# Power.net
KiCad netlist of a schematic drawn in Altium Designer
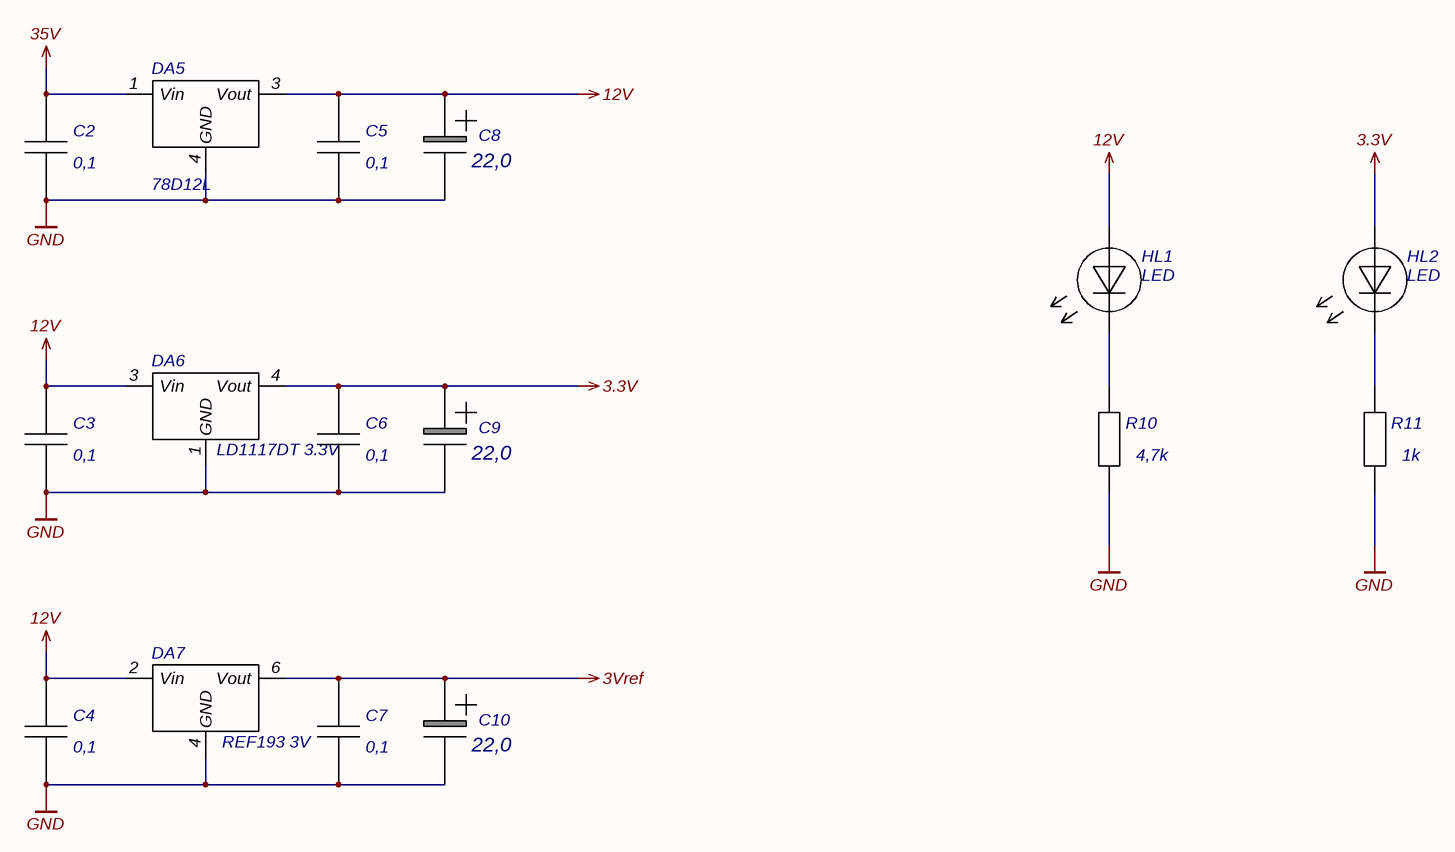
[diagram p0: Power.SchDoc]

(export (version "E")
  (design (tool "Eeschema 10.0.6"))
  (components
    (comp (ref "C2")
      (value "0,1")
      (footprint "С0805")
      (description "Чип-конденсатор")
      (libsource (lib "Passive") (part "Chip Capasitor"))
    )
    (comp (ref "C3")
      (value "0,1")
      (footprint "С0805")
      (description "Чип-конденсатор")
      (libsource (lib "Passive") (part "Chip Capasitor"))
    )
    (comp (ref "C4")
      (value "0,1")
      (footprint "С0805")
      (description "Чип-конденсатор")
      (libsource (lib "Passive") (part "Chip Capasitor"))
    )
    (comp (ref "C5")
      (value "0,1")
      (footprint "С0805")
      (description "Чип-конденсатор")
      (libsource (lib "Passive") (part "Chip Capasitor"))
    )
    (comp (ref "C6")
      (value "0,1")
      (footprint "С0805")
      (description "Чип-конденсатор")
      (libsource (lib "Passive") (part "Chip Capasitor"))
    )
    (comp (ref "C7")
      (value "0,1")
      (footprint "С0805")
      (description "Чип-конденсатор")
      (libsource (lib "Passive") (part "Chip Capasitor"))
    )
    (comp (ref "C8")
      (value "22,0")
      (footprint "C_tant 3(С-type)")
      (description "Чип конденсатор (3/C) тант.")
      (fields (field (name "MANUFACTURER") "KEMET") (field (name "PARTNUMBER") "Т491С226К010АТ"))
      (libsource (lib "Passive") (part "К53-67 (3/C)"))
    )
    (comp (ref "C9")
      (value "22,0")
      (footprint "C_tant 3(С-type)")
      (description "Чип конденсатор (3/C) тант.")
      (fields (field (name "MANUFACTURER") "KEMET") (field (name "PARTNUMBER") "Т491С226К010АТ"))
      (libsource (lib "Passive") (part "К53-67 (3/C)"))
    )
    (comp (ref "C10")
      (value "22,0")
      (footprint "C_tant 3(С-type)")
      (description "Чип конденсатор (3/C) тант.")
      (fields (field (name "MANUFACTURER") "KEMET") (field (name "PARTNUMBER") "Т491С226К010АТ"))
      (libsource (lib "Passive") (part "К53-67 (3/C)"))
    )
    (comp (ref "DA5")
      (value "78D12L")
      (footprint "DPAK")
      (description "Стабилизатор напряжения, 12В")
      (fields (field (name "MANUFACTURER") "UTD Semiconductor Co.,Ltd"))
      (libsource (lib "Schlib") (part "78D12L"))
    )
    (comp (ref "DA6")
      (value "LD1117DT 3.3V")
      (footprint "DPAK")
      (description "LDO-регулятор напряжения, 3.3В")
      (fields (field (name "MANUFACTURER") "STMicroelectronics"))
      (libsource (lib "Schlib") (part "LD1117DT33TR"))
    )
    (comp (ref "DA7")
      (value "REF193 3V")
      (footprint "SOP-8 (SOIC)")
      (description "Источник опорного напряжения, 3В")
      (fields (field (name "MANUFACTURER") "Analog Devices"))
      (libsource (lib "Schlib") (part "REF193"))
    )
    (comp (ref "HL1")
      (value "LED")
      (footprint "LED 5mm (L-7113IT)")
      (description "Светодиод, d=5мм")
      (fields (field (name "MANUFACTURER") "Kingbright"))
      (libsource (lib "Schlib") (part "LED"))
    )
    (comp (ref "HL2")
      (value "LED")
      (footprint "LED 5mm (L-7113IT)")
      (description "Светодиод, d=5мм")
      (fields (field (name "MANUFACTURER") "Kingbright"))
      (libsource (lib "Schlib") (part "LED"))
    )
    (comp (ref "R10")
      (value "4,7k")
      (footprint "R0603")
      (description "Чип-резистор")
      (libsource (lib "Passive") (part "Chip Resistor"))
    )
    (comp (ref "R11")
      (value "1k")
      (footprint "R0603")
      (description "Чип-резистор")
      (libsource (lib "Passive") (part "Chip Resistor"))
    )
  )
  (nets
    (net (code "1") (name "3.3V") (class "Default")
      (node (ref "C6") (pin "2") (pinfunction "2_2") (pintype "passive"))
      (node (ref "C9") (pin "1") (pinfunction "1_1") (pintype "passive"))
      (node (ref "DA6") (pin "4") (pinfunction "Vout_4") (pintype "passive"))
      (node (ref "HL2") (pin "2") (pinfunction "A_2") (pintype "passive"))
    )
    (net (code "2") (name "3Vref") (class "Default")
      (node (ref "C10") (pin "1") (pinfunction "1_1") (pintype "passive"))
      (node (ref "C7") (pin "2") (pinfunction "2_2") (pintype "passive"))
      (node (ref "DA7") (pin "6") (pinfunction "Vout_6") (pintype "passive"))
    )
    (net (code "3") (name "12V") (class "Default")
      (node (ref "C3") (pin "2") (pinfunction "2_2") (pintype "passive"))
      (node (ref "C4") (pin "2") (pinfunction "2_2") (pintype "passive"))
      (node (ref "C5") (pin "2") (pinfunction "2_2") (pintype "passive"))
      (node (ref "C8") (pin "1") (pinfunction "1_1") (pintype "passive"))
      (node (ref "DA5") (pin "3") (pinfunction "Vout_3") (pintype "passive"))
      (node (ref "DA6") (pin "3") (pinfunction "Vin_3") (pintype "passive"))
      (node (ref "DA7") (pin "2") (pinfunction "Vin_2") (pintype "passive"))
      (node (ref "HL1") (pin "2") (pinfunction "A_2") (pintype "passive"))
    )
    (net (code "4") (name "35V") (class "Default")
      (node (ref "C2") (pin "2") (pinfunction "2_2") (pintype "passive"))
      (node (ref "DA5") (pin "1") (pinfunction "Vin_1") (pintype "passive"))
    )
    (net (code "5") (name "GND") (class "Default")
      (node (ref "C10") (pin "2") (pinfunction "2_2") (pintype "passive"))
      (node (ref "C2") (pin "1") (pinfunction "1_1") (pintype "passive"))
      (node (ref "C3") (pin "1") (pinfunction "1_1") (pintype "passive"))
      (node (ref "C4") (pin "1") (pinfunction "1_1") (pintype "passive"))
      (node (ref "C5") (pin "1") (pinfunction "1_1") (pintype "passive"))
      (node (ref "C6") (pin "1") (pinfunction "1_1") (pintype "passive"))
      (node (ref "C7") (pin "1") (pinfunction "1_1") (pintype "passive"))
      (node (ref "C8") (pin "2") (pinfunction "2_2") (pintype "passive"))
      (node (ref "C9") (pin "2") (pinfunction "2_2") (pintype "passive"))
      (node (ref "DA5") (pin "4") (pinfunction "GND_4") (pintype "passive"))
      (node (ref "DA6") (pin "1") (pinfunction "GND_1") (pintype "passive"))
      (node (ref "DA7") (pin "4") (pinfunction "GND_4") (pintype "passive"))
      (node (ref "R10") (pin "1") (pinfunction "1_1") (pintype "passive"))
      (node (ref "R11") (pin "1") (pinfunction "1_1") (pintype "passive"))
    )
    (net (code "6") (name "Net-(HL1-K)") (class "Default")
      (node (ref "HL1") (pin "1") (pinfunction "K_1") (pintype "passive"))
      (node (ref "R10") (pin "2") (pinfunction "2_2") (pintype "passive"))
    )
    (net (code "7") (name "Net-(HL2-K)") (class "Default")
      (node (ref "HL2") (pin "1") (pinfunction "K_1") (pintype "passive"))
      (node (ref "R11") (pin "2") (pinfunction "2_2") (pintype "passive"))
    )
  )
)
